# HV_DAC_8ch_FPGA.net
KiCad netlist of a schematic drawn in Altium Designer
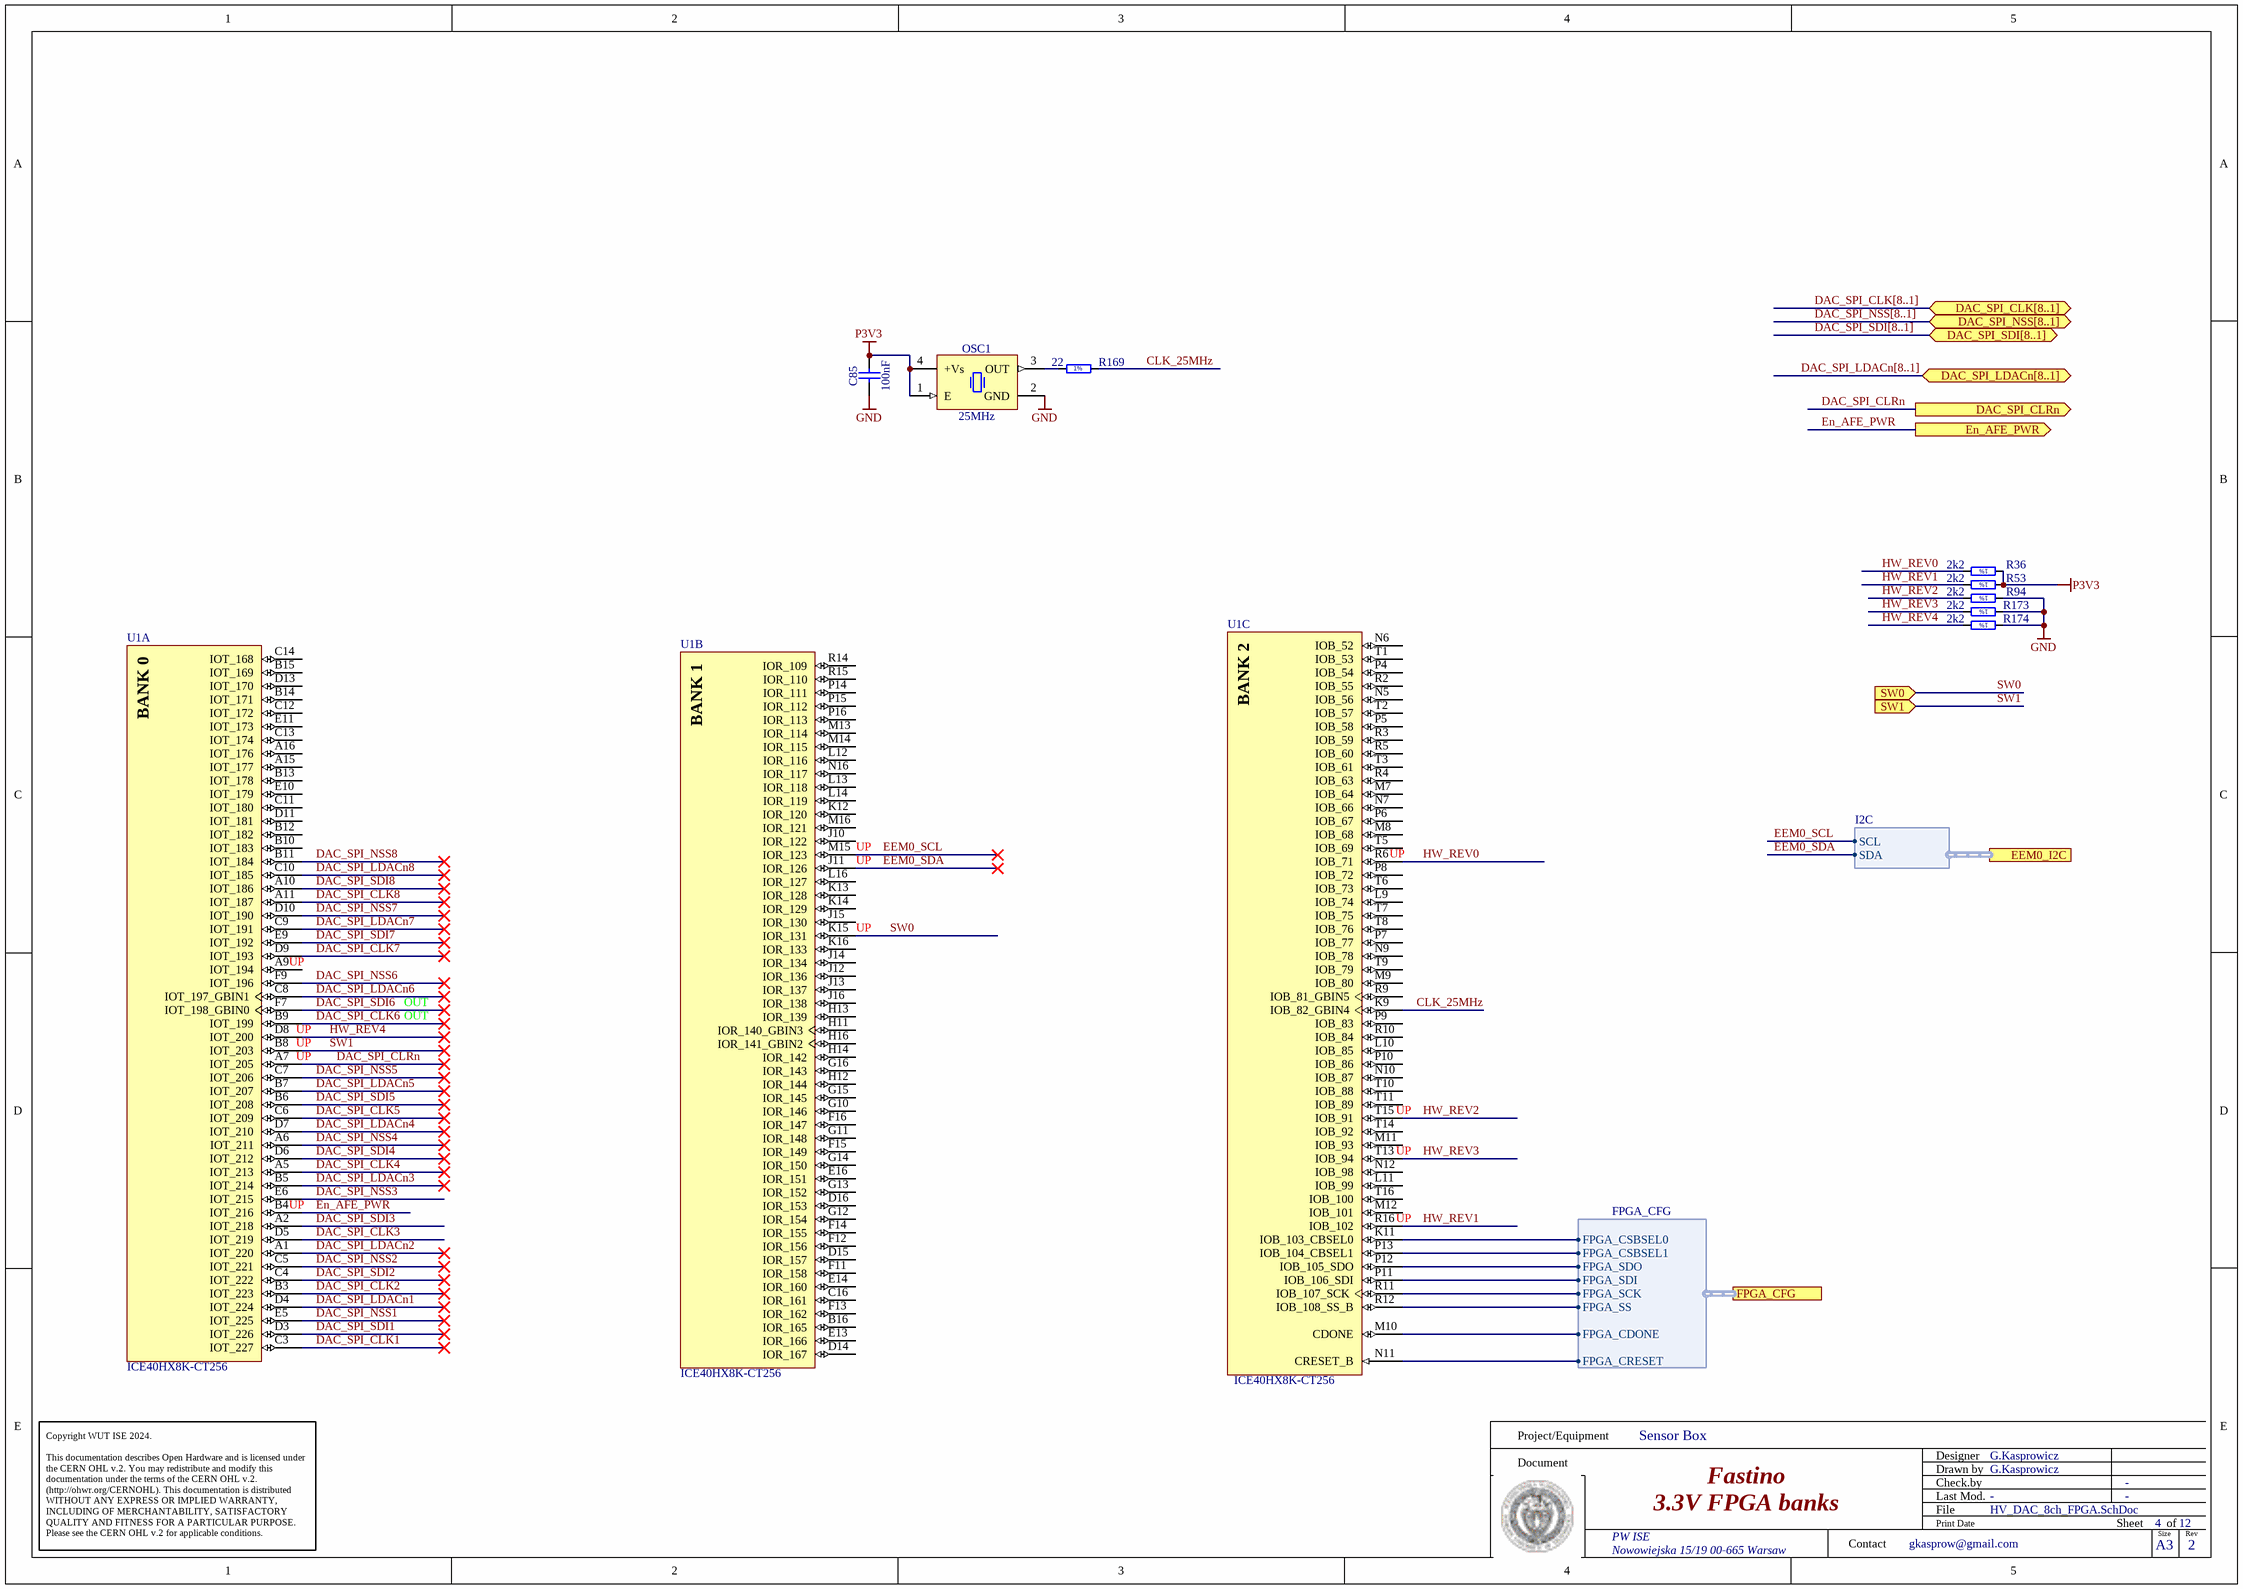
[diagram p0: HV_DAC_8ch_FPGA.SchDoc]

(export (version "E")
  (design (tool "Eeschema 10.0.6"))
  (components
    (comp (ref "C85")
      (value "100nF")
      (footprint "CAPC1005X55N")
      (description "Non-polarised capacitor")
      (fields
        (field (name "PART NUMBER") "CC0402_100NF_16V_10%_X5R")
        (field (name "VOLTAGE") "16V")
        (field (name "AUTHOR") "CERN DEM JLC")
      )
      (libsource (lib "Capacitors") (part "Capacitor - non polarized"))
    )
    (comp (ref "OSC1")
      (value "25MHz")
      (footprint "OSC_IQD_CFPS-39")
      (description "Oscillator 4 pins 1=E 2=GND 3=OUT 4=+Vs")
      (fields
        (field (name "PART NUMBER") "OSC_25MHZ_IQD_LFSPXO025165")
        (field (name "MANUFACTURER") "IQD FREQUENCY PRODUCTS")
        (field (name "AUTHOR") "CERN DEM JLC")
      )
      (libsource (lib "ICs And Semiconductors") (part "Oscillator 1E 2GND 3OUT 4Vs"))
    )
    (comp (ref "R36")
      (value "2k2")
      (footprint "RESC1005X40N")
      (description "Resistor - 1%")
      (fields
        (field (name "PART NUMBER") "R0402_2K2_1%_0.0625W_100PPM")
        (field (name "POWER") "0.0625W")
        (field (name "AUTHOR") "CERN DEM JLC")
      )
      (libsource (lib "Resistors") (part "Resistor - 1%"))
    )
    (comp (ref "R53")
      (value "2k2")
      (footprint "RESC1005X40N")
      (description "Resistor - 1%")
      (fields
        (field (name "PART NUMBER") "R0402_2K2_1%_0.0625W_100PPM")
        (field (name "POWER") "0.0625W")
        (field (name "AUTHOR") "CERN DEM JLC")
      )
      (libsource (lib "Resistors") (part "Resistor - 1%"))
    )
    (comp (ref "R94")
      (value "2k2")
      (footprint "RESC1005X40N")
      (description "Resistor - 1%")
      (fields
        (field (name "PART NUMBER") "R0402_2K2_1%_0.0625W_100PPM")
        (field (name "POWER") "0.0625W")
        (field (name "AUTHOR") "CERN DEM JLC")
      )
      (libsource (lib "Resistors") (part "Resistor - 1%"))
    )
    (comp (ref "R169")
      (value "22")
      (footprint "RESC1005X40N")
      (description "Resistor - 1%")
      (fields
        (field (name "PART NUMBER") "R0402_22R_1%_0.0625W_100PPM")
        (field (name "POWER") "0.0625W")
        (field (name "AUTHOR") "CERN DEM JLC")
      )
      (libsource (lib "Resistors") (part "Resistor - 1%"))
    )
    (comp (ref "R173")
      (value "2k2")
      (footprint "RESC1005X40N")
      (description "Resistor - 1%")
      (fields
        (field (name "PART NUMBER") "R0402_2K2_1%_0.0625W_100PPM")
        (field (name "POWER") "0.0625W")
        (field (name "AUTHOR") "CERN DEM JLC")
      )
      (libsource (lib "Resistors") (part "Resistor - 1%"))
    )
    (comp (ref "R174")
      (value "2k2")
      (footprint "RESC1005X40N")
      (description "Resistor - 1%")
      (fields
        (field (name "PART NUMBER") "R0402_2K2_1%_0.0625W_100PPM")
        (field (name "POWER") "0.0625W")
        (field (name "AUTHOR") "CERN DEM JLC")
      )
      (libsource (lib "Resistors") (part "Resistor - 1%"))
    )
    (comp (ref "U1")
      (value "ICE40HX8K-CT256")
      (footprint "LATC-caBGA-256")
      (fields (field (name "MANUFACTURER") "Lattice Semiconductor"))
      (libsource (lib "Altium Content Vault") (part "LATC-HX8K-caBGA-256"))
    )
  )
  (nets
    (net (code "3") (name "/CLK_25MHz") (class "Default")
      (node (ref "R169") (pin "2") (pinfunction "2_2") (pintype "passive"))
      (node (ref "U1") (pin "K9") (pinfunction "IOB_82_GBIN4_K9") (pintype "bidirectional"))
    )
    (net (code "4") (name "/DAC_SPI_CLK1") (class "Default")
      (node (ref "U1") (pin "C3") (pinfunction "IOT_227_C3") (pintype "bidirectional+no_connect"))
    )
    (net (code "5") (name "/DAC_SPI_CLK2") (class "Default")
      (node (ref "U1") (pin "B3") (pinfunction "IOT_223_B3") (pintype "bidirectional+no_connect"))
    )
    (net (code "6") (name "/DAC_SPI_CLK3") (class "Default")
      (node (ref "U1") (pin "D5") (pinfunction "IOT_219_D5") (pintype "bidirectional"))
    )
    (net (code "7") (name "/DAC_SPI_CLK4") (class "Default")
      (node (ref "U1") (pin "A5") (pinfunction "IOT_213_A5") (pintype "bidirectional+no_connect"))
    )
    (net (code "8") (name "/DAC_SPI_CLK5") (class "Default")
      (node (ref "U1") (pin "C6") (pinfunction "IOT_209_C6") (pintype "bidirectional+no_connect"))
    )
    (net (code "9") (name "/DAC_SPI_CLK6") (class "Default")
      (node (ref "U1") (pin "B9") (pinfunction "IOT_199_B9") (pintype "bidirectional+no_connect"))
    )
    (net (code "10") (name "/DAC_SPI_CLK7") (class "Default")
      (node (ref "U1") (pin "D9") (pinfunction "IOT_193_D9") (pintype "bidirectional+no_connect"))
    )
    (net (code "11") (name "/DAC_SPI_CLK8") (class "Default")
      (node (ref "U1") (pin "A11") (pinfunction "IOT_187_A11") (pintype "bidirectional+no_connect"))
    )
    (net (code "13") (name "/DAC_SPI_CLRn") (class "Default")
      (node (ref "U1") (pin "A7") (pinfunction "IOT_205_A7") (pintype "bidirectional"))
    )
    (net (code "14") (name "/DAC_SPI_LDACn1") (class "Default")
      (node (ref "U1") (pin "D4") (pinfunction "IOT_224_D4") (pintype "bidirectional+no_connect"))
    )
    (net (code "15") (name "/DAC_SPI_LDACn2") (class "Default")
      (node (ref "U1") (pin "A1") (pinfunction "IOT_220_A1") (pintype "bidirectional+no_connect"))
    )
    (net (code "16") (name "/DAC_SPI_LDACn3") (class "Default")
      (node (ref "U1") (pin "B5") (pinfunction "IOT_214_B5") (pintype "bidirectional+no_connect"))
    )
    (net (code "17") (name "/DAC_SPI_LDACn4") (class "Default")
      (node (ref "U1") (pin "D7") (pinfunction "IOT_210_D7") (pintype "bidirectional+no_connect"))
    )
    (net (code "18") (name "/DAC_SPI_LDACn5") (class "Default")
      (node (ref "U1") (pin "B7") (pinfunction "IOT_207_B7") (pintype "bidirectional+no_connect"))
    )
    (net (code "19") (name "/DAC_SPI_LDACn6") (class "Default")
      (node (ref "U1") (pin "C8") (pinfunction "IOT_197_GBIN1_C8") (pintype "bidirectional+no_connect"))
    )
    (net (code "20") (name "/DAC_SPI_LDACn7") (class "Default")
      (node (ref "U1") (pin "C9") (pinfunction "IOT_191_C9") (pintype "bidirectional+no_connect"))
    )
    (net (code "21") (name "/DAC_SPI_LDACn8") (class "Default")
      (node (ref "U1") (pin "C10") (pinfunction "IOT_185_C10") (pintype "bidirectional+no_connect"))
    )
    (net (code "23") (name "/DAC_SPI_NSS1") (class "Default")
      (node (ref "U1") (pin "E5") (pinfunction "IOT_225_E5") (pintype "bidirectional+no_connect"))
    )
    (net (code "24") (name "/DAC_SPI_NSS2") (class "Default")
      (node (ref "U1") (pin "C5") (pinfunction "IOT_221_C5") (pintype "bidirectional+no_connect"))
    )
    (net (code "25") (name "/DAC_SPI_NSS3") (class "Default")
      (node (ref "U1") (pin "E6") (pinfunction "IOT_215_E6") (pintype "bidirectional"))
    )
    (net (code "26") (name "/DAC_SPI_NSS4") (class "Default")
      (node (ref "U1") (pin "A6") (pinfunction "IOT_211_A6") (pintype "bidirectional+no_connect"))
    )
    (net (code "27") (name "/DAC_SPI_NSS5") (class "Default")
      (node (ref "U1") (pin "C7") (pinfunction "IOT_206_C7") (pintype "bidirectional+no_connect"))
    )
    (net (code "28") (name "/DAC_SPI_NSS6") (class "Default")
      (node (ref "U1") (pin "F9") (pinfunction "IOT_196_F9") (pintype "bidirectional+no_connect"))
    )
    (net (code "29") (name "/DAC_SPI_NSS7") (class "Default")
      (node (ref "U1") (pin "D10") (pinfunction "IOT_190_D10") (pintype "bidirectional+no_connect"))
    )
    (net (code "30") (name "/DAC_SPI_NSS8") (class "Default")
      (node (ref "U1") (pin "B11") (pinfunction "IOT_184_B11") (pintype "bidirectional+no_connect"))
    )
    (net (code "32") (name "/DAC_SPI_SDI1") (class "Default")
      (node (ref "U1") (pin "D3") (pinfunction "IOT_226_D3") (pintype "bidirectional+no_connect"))
    )
    (net (code "33") (name "/DAC_SPI_SDI2") (class "Default")
      (node (ref "U1") (pin "C4") (pinfunction "IOT_222_C4") (pintype "bidirectional+no_connect"))
    )
    (net (code "34") (name "/DAC_SPI_SDI3") (class "Default")
      (node (ref "U1") (pin "A2") (pinfunction "IOT_218_A2") (pintype "bidirectional"))
    )
    (net (code "35") (name "/DAC_SPI_SDI4") (class "Default")
      (node (ref "U1") (pin "D6") (pinfunction "IOT_212_D6") (pintype "bidirectional+no_connect"))
    )
    (net (code "36") (name "/DAC_SPI_SDI5") (class "Default")
      (node (ref "U1") (pin "B6") (pinfunction "IOT_208_B6") (pintype "bidirectional+no_connect"))
    )
    (net (code "37") (name "/DAC_SPI_SDI6") (class "Default")
      (node (ref "U1") (pin "F7") (pinfunction "IOT_198_GBIN0_F7") (pintype "bidirectional+no_connect"))
    )
    (net (code "38") (name "/DAC_SPI_SDI7") (class "Default")
      (node (ref "U1") (pin "E9") (pinfunction "IOT_192_E9") (pintype "bidirectional+no_connect"))
    )
    (net (code "39") (name "/DAC_SPI_SDI8") (class "Default")
      (node (ref "U1") (pin "A10") (pinfunction "IOT_186_A10") (pintype "bidirectional+no_connect"))
    )
    (net (code "41") (name "/EEM0_SCL") (class "Default")
      (node (ref "U1") (pin "M15") (pinfunction "IOR_123_M15") (pintype "bidirectional"))
    )
    (net (code "42") (name "/EEM0_SDA") (class "Default")
      (node (ref "U1") (pin "J11") (pinfunction "IOR_126_J11") (pintype "bidirectional"))
    )
    (net (code "43") (name "/En_AFE_PWR") (class "Default")
      (node (ref "U1") (pin "B4") (pinfunction "IOT_216_B4") (pintype "bidirectional"))
    )
    (net (code "44") (name "/FPGA_CDONE") (class "Default")
      (node (ref "U1") (pin "M10") (pinfunction "CDONE_M10") (pintype "bidirectional"))
    )
    (net (code "45") (name "/FPGA_CRESET") (class "Default")
      (node (ref "U1") (pin "N11") (pinfunction "CRESET_B_N11") (pintype "input"))
    )
    (net (code "46") (name "/FPGA_CSBSEL0") (class "Default")
      (node (ref "U1") (pin "K11") (pinfunction "IOB_103_CBSEL0_K11") (pintype "bidirectional"))
    )
    (net (code "47") (name "/FPGA_CSBSEL1") (class "Default")
      (node (ref "U1") (pin "P13") (pinfunction "IOB_104_CBSEL1_P13") (pintype "bidirectional"))
    )
    (net (code "48") (name "/FPGA_SCK") (class "Default")
      (node (ref "U1") (pin "R11") (pinfunction "IOB_107_SCK_R11") (pintype "bidirectional"))
    )
    (net (code "49") (name "/FPGA_SDI") (class "Default")
      (node (ref "U1") (pin "P11") (pinfunction "IOB_106_SDI_P11") (pintype "bidirectional"))
    )
    (net (code "50") (name "/FPGA_SDO") (class "Default")
      (node (ref "U1") (pin "P12") (pinfunction "IOB_105_SDO_P12") (pintype "bidirectional"))
    )
    (net (code "51") (name "/FPGA_SS") (class "Default")
      (node (ref "U1") (pin "R12") (pinfunction "IOB_108_SS_B_R12") (pintype "bidirectional"))
    )
    (net (code "52") (name "/HW_REV0") (class "Default")
      (node (ref "R36") (pin "2") (pinfunction "2_2") (pintype "passive"))
      (node (ref "U1") (pin "R6") (pinfunction "IOB_71_R6") (pintype "bidirectional"))
    )
    (net (code "53") (name "/HW_REV1") (class "Default")
      (node (ref "R53") (pin "2") (pinfunction "2_2") (pintype "passive"))
      (node (ref "U1") (pin "R16") (pinfunction "IOB_102_R16") (pintype "bidirectional"))
    )
    (net (code "54") (name "/HW_REV2") (class "Default")
      (node (ref "R94") (pin "2") (pinfunction "2_2") (pintype "passive"))
      (node (ref "U1") (pin "T15") (pinfunction "IOB_91_T15") (pintype "bidirectional"))
    )
    (net (code "55") (name "/HW_REV3") (class "Default")
      (node (ref "R173") (pin "2") (pinfunction "2_2") (pintype "passive"))
      (node (ref "U1") (pin "T13") (pinfunction "IOB_94_T13") (pintype "bidirectional"))
    )
    (net (code "56") (name "/HW_REV4") (class "Default")
      (node (ref "R174") (pin "2") (pinfunction "2_2") (pintype "passive"))
      (node (ref "U1") (pin "D8") (pinfunction "IOT_200_D8") (pintype "bidirectional"))
    )
    (net (code "57") (name "/SW0") (class "Default")
      (node (ref "U1") (pin "K15") (pinfunction "IOR_131_K15") (pintype "bidirectional"))
    )
    (net (code "58") (name "/SW1") (class "Default")
      (node (ref "U1") (pin "B8") (pinfunction "IOT_203_B8") (pintype "bidirectional"))
    )
    (net (code "61") (name "GND") (class "Default")
      (node (ref "C85") (pin "1") (pinfunction "1_1") (pintype "passive"))
      (node (ref "OSC1") (pin "2") (pinfunction "GND_2") (pintype "power_in"))
      (node (ref "R173") (pin "1") (pinfunction "1_1") (pintype "passive"))
      (node (ref "R174") (pin "1") (pinfunction "1_1") (pintype "passive"))
      (node (ref "R94") (pin "1") (pinfunction "1_1") (pintype "passive"))
    )
    (net (code "62") (name "Net-(OSC1-OUT)") (class "Default")
      (node (ref "OSC1") (pin "3") (pinfunction "OUT_3") (pintype "output"))
      (node (ref "R169") (pin "1") (pinfunction "1_1") (pintype "passive"))
    )
    (net (code "63") (name "P3V3") (class "Default")
      (node (ref "C85") (pin "2") (pinfunction "2_2") (pintype "passive"))
      (node (ref "OSC1") (pin "1") (pinfunction "E_1") (pintype "input"))
      (node (ref "OSC1") (pin "4") (pinfunction "+Vs_4") (pintype "power_in"))
      (node (ref "R36") (pin "1") (pinfunction "1_1") (pintype "passive"))
      (node (ref "R53") (pin "1") (pinfunction "1_1") (pintype "passive"))
    )
    (net (code "64") (name "unconnected-(U1A-IOT_168-PadC14)") (class "Default")
      (node (ref "U1") (pin "C14") (pinfunction "IOT_168_C14") (pintype "bidirectional"))
    )
    (net (code "65") (name "unconnected-(U1A-IOT_169-PadB15)") (class "Default")
      (node (ref "U1") (pin "B15") (pinfunction "IOT_169_B15") (pintype "bidirectional"))
    )
    (net (code "66") (name "unconnected-(U1A-IOT_170-PadD13)") (class "Default")
      (node (ref "U1") (pin "D13") (pinfunction "IOT_170_D13") (pintype "bidirectional"))
    )
    (net (code "67") (name "unconnected-(U1A-IOT_171-PadB14)") (class "Default")
      (node (ref "U1") (pin "B14") (pinfunction "IOT_171_B14") (pintype "bidirectional"))
    )
    (net (code "68") (name "unconnected-(U1A-IOT_172-PadC12)") (class "Default")
      (node (ref "U1") (pin "C12") (pinfunction "IOT_172_C12") (pintype "bidirectional"))
    )
    (net (code "69") (name "unconnected-(U1A-IOT_173-PadE11)") (class "Default")
      (node (ref "U1") (pin "E11") (pinfunction "IOT_173_E11") (pintype "bidirectional"))
    )
    (net (code "70") (name "unconnected-(U1A-IOT_174-PadC13)") (class "Default")
      (node (ref "U1") (pin "C13") (pinfunction "IOT_174_C13") (pintype "bidirectional"))
    )
    (net (code "71") (name "unconnected-(U1A-IOT_176-PadA16)") (class "Default")
      (node (ref "U1") (pin "A16") (pinfunction "IOT_176_A16") (pintype "bidirectional"))
    )
    (net (code "72") (name "unconnected-(U1A-IOT_177-PadA15)") (class "Default")
      (node (ref "U1") (pin "A15") (pinfunction "IOT_177_A15") (pintype "bidirectional"))
    )
    (net (code "73") (name "unconnected-(U1A-IOT_178-PadB13)") (class "Default")
      (node (ref "U1") (pin "B13") (pinfunction "IOT_178_B13") (pintype "bidirectional"))
    )
    (net (code "74") (name "unconnected-(U1A-IOT_179-PadE10)") (class "Default")
      (node (ref "U1") (pin "E10") (pinfunction "IOT_179_E10") (pintype "bidirectional"))
    )
    (net (code "75") (name "unconnected-(U1A-IOT_180-PadC11)") (class "Default")
      (node (ref "U1") (pin "C11") (pinfunction "IOT_180_C11") (pintype "bidirectional"))
    )
    (net (code "76") (name "unconnected-(U1A-IOT_181-PadD11)") (class "Default")
      (node (ref "U1") (pin "D11") (pinfunction "IOT_181_D11") (pintype "bidirectional"))
    )
    (net (code "77") (name "unconnected-(U1A-IOT_182-PadB12)") (class "Default")
      (node (ref "U1") (pin "B12") (pinfunction "IOT_182_B12") (pintype "bidirectional"))
    )
    (net (code "78") (name "unconnected-(U1A-IOT_183-PadB10)") (class "Default")
      (node (ref "U1") (pin "B10") (pinfunction "IOT_183_B10") (pintype "bidirectional"))
    )
    (net (code "79") (name "unconnected-(U1A-IOT_194-PadA9)") (class "Default")
      (node (ref "U1") (pin "A9") (pinfunction "IOT_194_A9") (pintype "bidirectional"))
    )
    (net (code "80") (name "unconnected-(U1B-IOR_109-PadR14)") (class "Default")
      (node (ref "U1") (pin "R14") (pinfunction "IOR_109_R14") (pintype "bidirectional"))
    )
    (net (code "81") (name "unconnected-(U1B-IOR_110-PadR15)") (class "Default")
      (node (ref "U1") (pin "R15") (pinfunction "IOR_110_R15") (pintype "bidirectional"))
    )
    (net (code "82") (name "unconnected-(U1B-IOR_111-PadP14)") (class "Default")
      (node (ref "U1") (pin "P14") (pinfunction "IOR_111_P14") (pintype "bidirectional"))
    )
    (net (code "83") (name "unconnected-(U1B-IOR_112-PadP15)") (class "Default")
      (node (ref "U1") (pin "P15") (pinfunction "IOR_112_P15") (pintype "bidirectional"))
    )
    (net (code "84") (name "unconnected-(U1B-IOR_113-PadP16)") (class "Default")
      (node (ref "U1") (pin "P16") (pinfunction "IOR_113_P16") (pintype "bidirectional"))
    )
    (net (code "85") (name "unconnected-(U1B-IOR_114-PadM13)") (class "Default")
      (node (ref "U1") (pin "M13") (pinfunction "IOR_114_M13") (pintype "bidirectional"))
    )
    (net (code "86") (name "unconnected-(U1B-IOR_115-PadM14)") (class "Default")
      (node (ref "U1") (pin "M14") (pinfunction "IOR_115_M14") (pintype "bidirectional"))
    )
    (net (code "87") (name "unconnected-(U1B-IOR_116-PadL12)") (class "Default")
      (node (ref "U1") (pin "L12") (pinfunction "IOR_116_L12") (pintype "bidirectional"))
    )
    (net (code "88") (name "unconnected-(U1B-IOR_117-PadN16)") (class "Default")
      (node (ref "U1") (pin "N16") (pinfunction "IOR_117_N16") (pintype "bidirectional"))
    )
    (net (code "89") (name "unconnected-(U1B-IOR_118-PadL13)") (class "Default")
      (node (ref "U1") (pin "L13") (pinfunction "IOR_118_L13") (pintype "bidirectional"))
    )
    (net (code "90") (name "unconnected-(U1B-IOR_119-PadL14)") (class "Default")
      (node (ref "U1") (pin "L14") (pinfunction "IOR_119_L14") (pintype "bidirectional"))
    )
    (net (code "91") (name "unconnected-(U1B-IOR_120-PadK12)") (class "Default")
      (node (ref "U1") (pin "K12") (pinfunction "IOR_120_K12") (pintype "bidirectional"))
    )
    (net (code "92") (name "unconnected-(U1B-IOR_121-PadM16)") (class "Default")
      (node (ref "U1") (pin "M16") (pinfunction "IOR_121_M16") (pintype "bidirectional"))
    )
    (net (code "93") (name "unconnected-(U1B-IOR_122-PadJ10)") (class "Default")
      (node (ref "U1") (pin "J10") (pinfunction "IOR_122_J10") (pintype "bidirectional"))
    )
    (net (code "94") (name "unconnected-(U1B-IOR_127-PadL16)") (class "Default")
      (node (ref "U1") (pin "L16") (pinfunction "IOR_127_L16") (pintype "bidirectional"))
    )
    (net (code "95") (name "unconnected-(U1B-IOR_128-PadK13)") (class "Default")
      (node (ref "U1") (pin "K13") (pinfunction "IOR_128_K13") (pintype "bidirectional"))
    )
    (net (code "96") (name "unconnected-(U1B-IOR_129-PadK14)") (class "Default")
      (node (ref "U1") (pin "K14") (pinfunction "IOR_129_K14") (pintype "bidirectional"))
    )
    (net (code "97") (name "unconnected-(U1B-IOR_130-PadJ15)") (class "Default")
      (node (ref "U1") (pin "J15") (pinfunction "IOR_130_J15") (pintype "bidirectional"))
    )
    (net (code "98") (name "unconnected-(U1B-IOR_133-PadK16)") (class "Default")
      (node (ref "U1") (pin "K16") (pinfunction "IOR_133_K16") (pintype "bidirectional"))
    )
    (net (code "99") (name "unconnected-(U1B-IOR_134-PadJ14)") (class "Default")
      (node (ref "U1") (pin "J14") (pinfunction "IOR_134_J14") (pintype "bidirectional"))
    )
    (net (code "100") (name "unconnected-(U1B-IOR_136-PadJ12)") (class "Default")
      (node (ref "U1") (pin "J12") (pinfunction "IOR_136_J12") (pintype "bidirectional"))
    )
    (net (code "101") (name "unconnected-(U1B-IOR_137-PadJ13)") (class "Default")
      (node (ref "U1") (pin "J13") (pinfunction "IOR_137_J13") (pintype "bidirectional"))
    )
    (net (code "102") (name "unconnected-(U1B-IOR_138-PadJ16)") (class "Default")
      (node (ref "U1") (pin "J16") (pinfunction "IOR_138_J16") (pintype "bidirectional"))
    )
    (net (code "103") (name "unconnected-(U1B-IOR_139-PadH13)") (class "Default")
      (node (ref "U1") (pin "H13") (pinfunction "IOR_139_H13") (pintype "bidirectional"))
    )
    (net (code "104") (name "unconnected-(U1B-IOR_140_GBIN3-PadH11)") (class "Default")
      (node (ref "U1") (pin "H11") (pinfunction "IOR_140_GBIN3_H11") (pintype "bidirectional"))
    )
    (net (code "105") (name "unconnected-(U1B-IOR_141_GBIN2-PadH16)") (class "Default")
      (node (ref "U1") (pin "H16") (pinfunction "IOR_141_GBIN2_H16") (pintype "bidirectional"))
    )
    (net (code "106") (name "unconnected-(U1B-IOR_142-PadH14)") (class "Default")
      (node (ref "U1") (pin "H14") (pinfunction "IOR_142_H14") (pintype "bidirectional"))
    )
    (net (code "107") (name "unconnected-(U1B-IOR_143-PadG16)") (class "Default")
      (node (ref "U1") (pin "G16") (pinfunction "IOR_143_G16") (pintype "bidirectional"))
    )
    (net (code "108") (name "unconnected-(U1B-IOR_144-PadH12)") (class "Default")
      (node (ref "U1") (pin "H12") (pinfunction "IOR_144_H12") (pintype "bidirectional"))
    )
    (net (code "109") (name "unconnected-(U1B-IOR_145-PadG15)") (class "Default")
      (node (ref "U1") (pin "G15") (pinfunction "IOR_145_G15") (pintype "bidirectional"))
    )
    (net (code "110") (name "unconnected-(U1B-IOR_146-PadG10)") (class "Default")
      (node (ref "U1") (pin "G10") (pinfunction "IOR_146_G10") (pintype "bidirectional"))
    )
    (net (code "111") (name "unconnected-(U1B-IOR_147-PadF16)") (class "Default")
      (node (ref "U1") (pin "F16") (pinfunction "IOR_147_F16") (pintype "bidirectional"))
    )
    (net (code "112") (name "unconnected-(U1B-IOR_148-PadG11)") (class "Default")
      (node (ref "U1") (pin "G11") (pinfunction "IOR_148_G11") (pintype "bidirectional"))
    )
    (net (code "113") (name "unconnected-(U1B-IOR_149-PadF15)") (class "Default")
      (node (ref "U1") (pin "F15") (pinfunction "IOR_149_F15") (pintype "bidirectional"))
    )
    (net (code "114") (name "unconnected-(U1B-IOR_150-PadG14)") (class "Default")
      (node (ref "U1") (pin "G14") (pinfunction "IOR_150_G14") (pintype "bidirectional"))
    )
    (net (code "115") (name "unconnected-(U1B-IOR_151-PadE16)") (class "Default")
      (node (ref "U1") (pin "E16") (pinfunction "IOR_151_E16") (pintype "bidirectional"))
    )
    (net (code "116") (name "unconnected-(U1B-IOR_152-PadG13)") (class "Default")
      (node (ref "U1") (pin "G13") (pinfunction "IOR_152_G13") (pintype "bidirectional"))
    )
    (net (code "117") (name "unconnected-(U1B-IOR_153-PadD16)") (class "Default")
      (node (ref "U1") (pin "D16") (pinfunction "IOR_153_D16") (pintype "bidirectional"))
    )
    (net (code "118") (name "unconnected-(U1B-IOR_154-PadG12)") (class "Default")
      (node (ref "U1") (pin "G12") (pinfunction "IOR_154_G12") (pintype "bidirectional"))
    )
    (net (code "119") (name "unconnected-(U1B-IOR_155-PadF14)") (class "Default")
      (node (ref "U1") (pin "F14") (pinfunction "IOR_155_F14") (pintype "bidirectional"))
    )
    (net (code "120") (name "unconnected-(U1B-IOR_156-PadF12)") (class "Default")
      (node (ref "U1") (pin "F12") (pinfunction "IOR_156_F12") (pintype "bidirectional"))
    )
    (net (code "121") (name "unconnected-(U1B-IOR_157-PadD15)") (class "Default")
      (node (ref "U1") (pin "D15") (pinfunction "IOR_157_D15") (pintype "bidirectional"))
    )
    (net (code "122") (name "unconnected-(U1B-IOR_158-PadF11)") (class "Default")
      (node (ref "U1") (pin "F11") (pinfunction "IOR_158_F11") (pintype "bidirectional"))
    )
    (net (code "123") (name "unconnected-(U1B-IOR_160-PadE14)") (class "Default")
      (node (ref "U1") (pin "E14") (pinfunction "IOR_160_E14") (pintype "bidirectional"))
    )
    (net (code "124") (name "unconnected-(U1B-IOR_161-PadC16)") (class "Default")
      (node (ref "U1") (pin "C16") (pinfunction "IOR_161_C16") (pintype "bidirectional"))
    )
    (net (code "125") (name "unconnected-(U1B-IOR_162-PadF13)") (class "Default")
      (node (ref "U1") (pin "F13") (pinfunction "IOR_162_F13") (pintype "bidirectional"))
    )
    (net (code "126") (name "unconnected-(U1B-IOR_165-PadB16)") (class "Default")
      (node (ref "U1") (pin "B16") (pinfunction "IOR_165_B16") (pintype "bidirectional"))
    )
    (net (code "127") (name "unconnected-(U1B-IOR_166-PadE13)") (class "Default")
      (node (ref "U1") (pin "E13") (pinfunction "IOR_166_E13") (pintype "bidirectional"))
    )
    (net (code "128") (name "unconnected-(U1B-IOR_167-PadD14)") (class "Default")
      (node (ref "U1") (pin "D14") (pinfunction "IOR_167_D14") (pintype "bidirectional"))
    )
    (net (code "129") (name "unconnected-(U1C-IOB_52-PadN6)") (class "Default")
      (node (ref "U1") (pin "N6") (pinfunction "IOB_52_N6") (pintype "bidirectional"))
    )
    (net (code "130") (name "unconnected-(U1C-IOB_53-PadT1)") (class "Default")
      (node (ref "U1") (pin "T1") (pinfunction "IOB_53_T1") (pintype "bidirectional"))
    )
    (net (code "131") (name "unconnected-(U1C-IOB_54-PadP4)") (class "Default")
      (node (ref "U1") (pin "P4") (pinfunction "IOB_54_P4") (pintype "bidirectional"))
    )
    (net (code "132") (name "unconnected-(U1C-IOB_55-PadR2)") (class "Default")
      (node (ref "U1") (pin "R2") (pinfunction "IOB_55_R2") (pintype "bidirectional"))
    )
    (net (code "133") (name "unconnected-(U1C-IOB_56-PadN5)") (class "Default")
      (node (ref "U1") (pin "N5") (pinfunction "IOB_56_N5") (pintype "bidirectional"))
    )
    (net (code "134") (name "unconnected-(U1C-IOB_57-PadT2)") (class "Default")
      (node (ref "U1") (pin "T2") (pinfunction "IOB_57_T2") (pintype "bidirectional"))
    )
    (net (code "135") (name "unconnected-(U1C-IOB_58-PadP5)") (class "Default")
      (node (ref "U1") (pin "P5") (pinfunction "IOB_58_P5") (pintype "bidirectional"))
    )
    (net (code "136") (name "unconnected-(U1C-IOB_59-PadR3)") (class "Default")
      (node (ref "U1") (pin "R3") (pinfunction "IOB_59_R3") (pintype "bidirectional"))
    )
    (net (code "137") (name "unconnected-(U1C-IOB_60-PadR5)") (class "Default")
      (node (ref "U1") (pin "R5") (pinfunction "IOB_60_R5") (pintype "bidirectional"))
    )
    (net (code "138") (name "unconnected-(U1C-IOB_61-PadT3)") (class "Default")
      (node (ref "U1") (pin "T3") (pinfunction "IOB_61_T3") (pintype "bidirectional"))
    )
    (net (code "139") (name "unconnected-(U1C-IOB_63-PadR4)") (class "Default")
      (node (ref "U1") (pin "R4") (pinfunction "IOB_63_R4") (pintype "bidirectional"))
    )
    (net (code "140") (name "unconnected-(U1C-IOB_64-PadM7)") (class "Default")
      (node (ref "U1") (pin "M7") (pinfunction "IOB_64_M7") (pintype "bidirectional"))
    )
    (net (code "141") (name "unconnected-(U1C-IOB_66-PadN7)") (class "Default")
      (node (ref "U1") (pin "N7") (pinfunction "IOB_66_N7") (pintype "bidirectional"))
    )
    (net (code "142") (name "unconnected-(U1C-IOB_67-PadP6)") (class "Default")
      (node (ref "U1") (pin "P6") (pinfunction "IOB_67_P6") (pintype "bidirectional"))
    )
    (net (code "143") (name "unconnected-(U1C-IOB_68-PadM8)") (class "Default")
      (node (ref "U1") (pin "M8") (pinfunction "IOB_68_M8") (pintype "bidirectional"))
    )
    (net (code "144") (name "unconnected-(U1C-IOB_69-PadT5)") (class "Default")
      (node (ref "U1") (pin "T5") (pinfunction "IOB_69_T5") (pintype "bidirectional"))
    )
    (net (code "145") (name "unconnected-(U1C-IOB_72-PadP8)") (class "Default")
      (node (ref "U1") (pin "P8") (pinfunction "IOB_72_P8") (pintype "bidirectional"))
    )
    (net (code "146") (name "unconnected-(U1C-IOB_73-PadT6)") (class "Default")
      (node (ref "U1") (pin "T6") (pinfunction "IOB_73_T6") (pintype "bidirectional"))
    )
    (net (code "147") (name "unconnected-(U1C-IOB_74-PadL9)") (class "Default")
      (node (ref "U1") (pin "L9") (pinfunction "IOB_74_L9") (pintype "bidirectional"))
    )
    (net (code "148") (name "unconnected-(U1C-IOB_75-PadT7)") (class "Default")
      (node (ref "U1") (pin "T7") (pinfunction "IOB_75_T7") (pintype "bidirectional"))
    )
    (net (code "149") (name "unconnected-(U1C-IOB_76-PadT8)") (class "Default")
      (node (ref "U1") (pin "T8") (pinfunction "IOB_76_T8") (pintype "bidirectional"))
    )
    (net (code "150") (name "unconnected-(U1C-IOB_77-PadP7)") (class "Default")
      (node (ref "U1") (pin "P7") (pinfunction "IOB_77_P7") (pintype "bidirectional"))
    )
    (net (code "151") (name "unconnected-(U1C-IOB_78-PadN9)") (class "Default")
      (node (ref "U1") (pin "N9") (pinfunction "IOB_78_N9") (pintype "bidirectional"))
    )
    (net (code "152") (name "unconnected-(U1C-IOB_79-PadT9)") (class "Default")
      (node (ref "U1") (pin "T9") (pinfunction "IOB_79_T9") (pintype "bidirectional"))
    )
    (net (code "153") (name "unconnected-(U1C-IOB_80-PadM9)") (class "Default")
      (node (ref "U1") (pin "M9") (pinfunction "IOB_80_M9") (pintype "bidirectional"))
    )
    (net (code "154") (name "unconnected-(U1C-IOB_81_GBIN5-PadR9)") (class "Default")
      (node (ref "U1") (pin "R9") (pinfunction "IOB_81_GBIN5_R9") (pintype "bidirectional"))
    )
    (net (code "155") (name "unconnected-(U1C-IOB_83-PadP9)") (class "Default")
      (node (ref "U1") (pin "P9") (pinfunction "IOB_83_P9") (pintype "bidirectional"))
    )
    (net (code "156") (name "unconnected-(U1C-IOB_84-PadR10)") (class "Default")
      (node (ref "U1") (pin "R10") (pinfunction "IOB_84_R10") (pintype "bidirectional"))
    )
    (net (code "157") (name "unconnected-(U1C-IOB_85-PadL10)") (class "Default")
      (node (ref "U1") (pin "L10") (pinfunction "IOB_85_L10") (pintype "bidirectional"))
    )
    (net (code "158") (name "unconnected-(U1C-IOB_86-PadP10)") (class "Default")
      (node (ref "U1") (pin "P10") (pinfunction "IOB_86_P10") (pintype "bidirectional"))
    )
    (net (code "159") (name "unconnected-(U1C-IOB_87-PadN10)") (class "Default")
      (node (ref "U1") (pin "N10") (pinfunction "IOB_87_N10") (pintype "bidirectional"))
    )
    (net (code "160") (name "unconnected-(U1C-IOB_88-PadT10)") (class "Default")
      (node (ref "U1") (pin "T10") (pinfunction "IOB_88_T10") (pintype "bidirectional"))
    )
    (net (code "161") (name "unconnected-(U1C-IOB_89-PadT11)") (class "Default")
      (node (ref "U1") (pin "T11") (pinfunction "IOB_89_T11") (pintype "bidirectional"))
    )
    (net (code "162") (name "unconnected-(U1C-IOB_92-PadT14)") (class "Default")
      (node (ref "U1") (pin "T14") (pinfunction "IOB_92_T14") (pintype "bidirectional"))
    )
    (net (code "163") (name "unconnected-(U1C-IOB_93-PadM11)") (class "Default")
      (node (ref "U1") (pin "M11") (pinfunction "IOB_93_M11") (pintype "bidirectional"))
    )
    (net (code "164") (name "unconnected-(U1C-IOB_98-PadN12)") (class "Default")
      (node (ref "U1") (pin "N12") (pinfunction "IOB_98_N12") (pintype "bidirectional"))
    )
    (net (code "165") (name "unconnected-(U1C-IOB_99-PadL11)") (class "Default")
      (node (ref "U1") (pin "L11") (pinfunction "IOB_99_L11") (pintype "bidirectional"))
    )
    (net (code "166") (name "unconnected-(U1C-IOB_100-PadT16)") (class "Default")
      (node (ref "U1") (pin "T16") (pinfunction "IOB_100_T16") (pintype "bidirectional"))
    )
    (net (code "167") (name "unconnected-(U1C-IOB_101-PadM12)") (class "Default")
      (node (ref "U1") (pin "M12") (pinfunction "IOB_101_M12") (pintype "bidirectional"))
    )
  )
)
